# Right_Ref_Sensor_SchDoc.net
KiCad netlist of a schematic drawn in Altium Designer
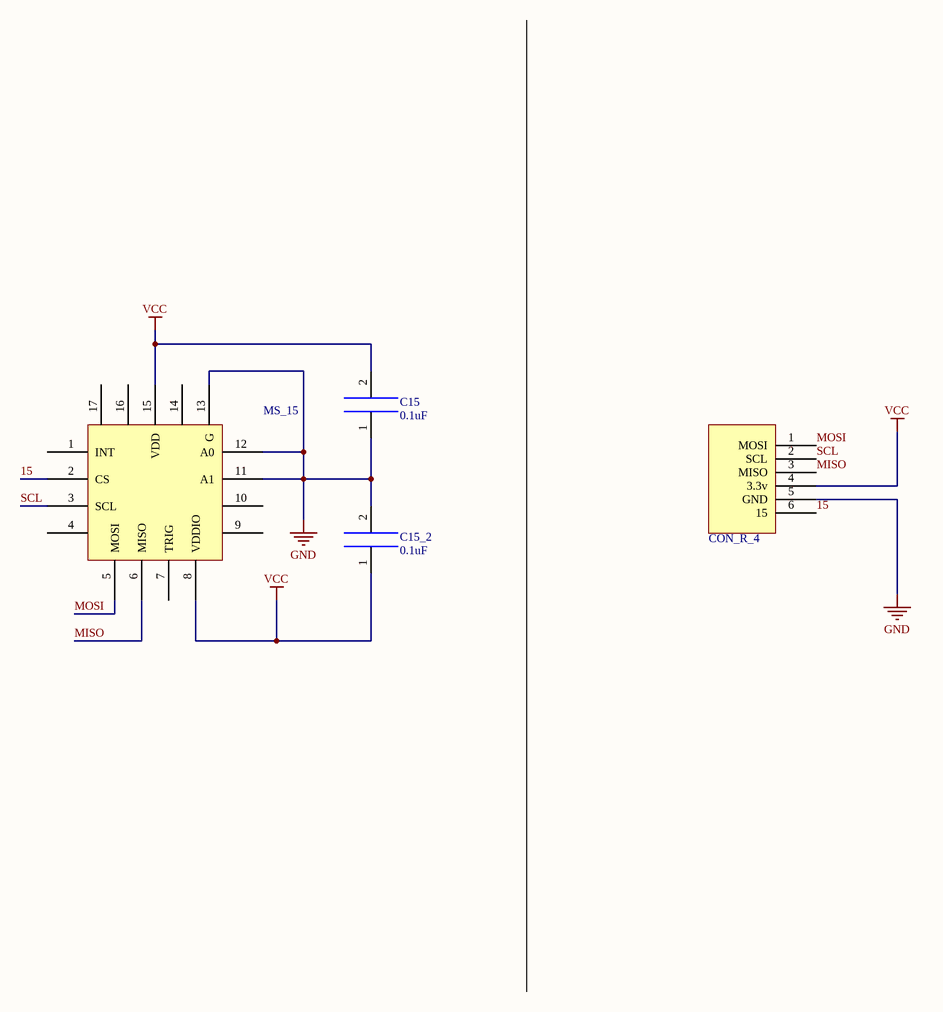
[diagram p0: Right_Ref_Sensor_SchDoc.SchDoc]

(export (version "E")
  (design (tool "Eeschema 10.0.6"))
  (components
    (comp (ref "C15")
      (value "0.1uF")
      (footprint "CAP_0603")
      (description "Capacitance")
      (libsource (lib "MagWaySchlib") (part "CAP"))
    )
    (comp (ref "C15_2")
      (value "0.1uF")
      (footprint "CAP_0603")
      (description "Capacitance")
      (libsource (lib "MagWaySchlib") (part "CAP"))
    )
    (comp (ref "CON_R_4")
      (value "PIN_right")
      (footprint "PIN_RIGHT_4")
      (libsource (lib "MagWaySchlib") (part "PIN_right_4"))
    )
    (comp (ref "MS_15")
      (value "MLX90393SLW ABA 011 RE")
      (footprint "MLX90393")
      (description "MLX90393 Sensor")
      (libsource (lib "MagWaySchlib") (part "MLX90393SLW ABA 011 RE"))
    )
  )
  (nets
    (net (code "1") (name "/15") (class "Default")
      (node (ref "CON_R_4") (pin "6") (pinfunction "15_6") (pintype "passive"))
      (node (ref "MS_15") (pin "2") (pinfunction "CS_2") (pintype "passive"))
    )
    (net (code "2") (name "/MISO") (class "Default")
      (node (ref "CON_R_4") (pin "3") (pinfunction "MISO_3") (pintype "passive"))
      (node (ref "MS_15") (pin "6") (pinfunction "MISO_6") (pintype "passive"))
    )
    (net (code "3") (name "/MOSI") (class "Default")
      (node (ref "CON_R_4") (pin "1") (pinfunction "MOSI_1") (pintype "passive"))
      (node (ref "MS_15") (pin "5") (pinfunction "MOSI_5") (pintype "passive"))
    )
    (net (code "4") (name "/SCL") (class "Default")
      (node (ref "CON_R_4") (pin "2") (pinfunction "SCL_2") (pintype "passive"))
      (node (ref "MS_15") (pin "3") (pinfunction "SCL_3") (pintype "passive"))
    )
    (net (code "5") (name "GND") (class "Default")
      (node (ref "C15") (pin "1") (pintype "passive"))
      (node (ref "C15_2") (pin "2") (pintype "passive"))
      (node (ref "CON_R_4") (pin "5") (pinfunction "GND_5") (pintype "passive"))
      (node (ref "MS_15") (pin "11") (pinfunction "A1_11") (pintype "passive"))
      (node (ref "MS_15") (pin "12") (pinfunction "A0_12") (pintype "passive"))
      (node (ref "MS_15") (pin "13") (pinfunction "G_13") (pintype "passive"))
    )
    (net (code "6") (name "VCC") (class "Default")
      (node (ref "C15") (pin "2") (pintype "passive"))
      (node (ref "C15_2") (pin "1") (pintype "passive"))
      (node (ref "CON_R_4") (pin "4") (pinfunction "3.3v_4") (pintype "passive"))
      (node (ref "MS_15") (pin "15") (pinfunction "VDD_15") (pintype "passive"))
      (node (ref "MS_15") (pin "8") (pinfunction "VDDIO_8") (pintype "passive"))
    )
    (net (code "7") (name "unconnected-(MS_15-INT-Pad1)") (class "Default")
      (node (ref "MS_15") (pin "1") (pinfunction "INT_1") (pintype "passive"))
    )
    (net (code "8") (name "unconnected-(MS_15-Pad4)") (class "Default")
      (node (ref "MS_15") (pin "4") (pintype "passive"))
    )
    (net (code "9") (name "unconnected-(MS_15-Pad9)") (class "Default")
      (node (ref "MS_15") (pin "9") (pintype "passive"))
    )
    (net (code "10") (name "unconnected-(MS_15-Pad10)") (class "Default")
      (node (ref "MS_15") (pin "10") (pintype "passive"))
    )
    (net (code "11") (name "unconnected-(MS_15-Pad14)") (class "Default")
      (node (ref "MS_15") (pin "14") (pintype "passive"))
    )
    (net (code "12") (name "unconnected-(MS_15-Pad16)") (class "Default")
      (node (ref "MS_15") (pin "16") (pintype "passive"))
    )
    (net (code "13") (name "unconnected-(MS_15-Pad17)") (class "Default")
      (node (ref "MS_15") (pin "17") (pintype "passive"))
    )
    (net (code "14") (name "unconnected-(MS_15-TRIG-Pad7)") (class "Default")
      (node (ref "MS_15") (pin "7") (pinfunction "TRIG_7") (pintype "passive"))
    )
  )
)
